# Interface.net
KiCad netlist of a schematic drawn in Altium Designer
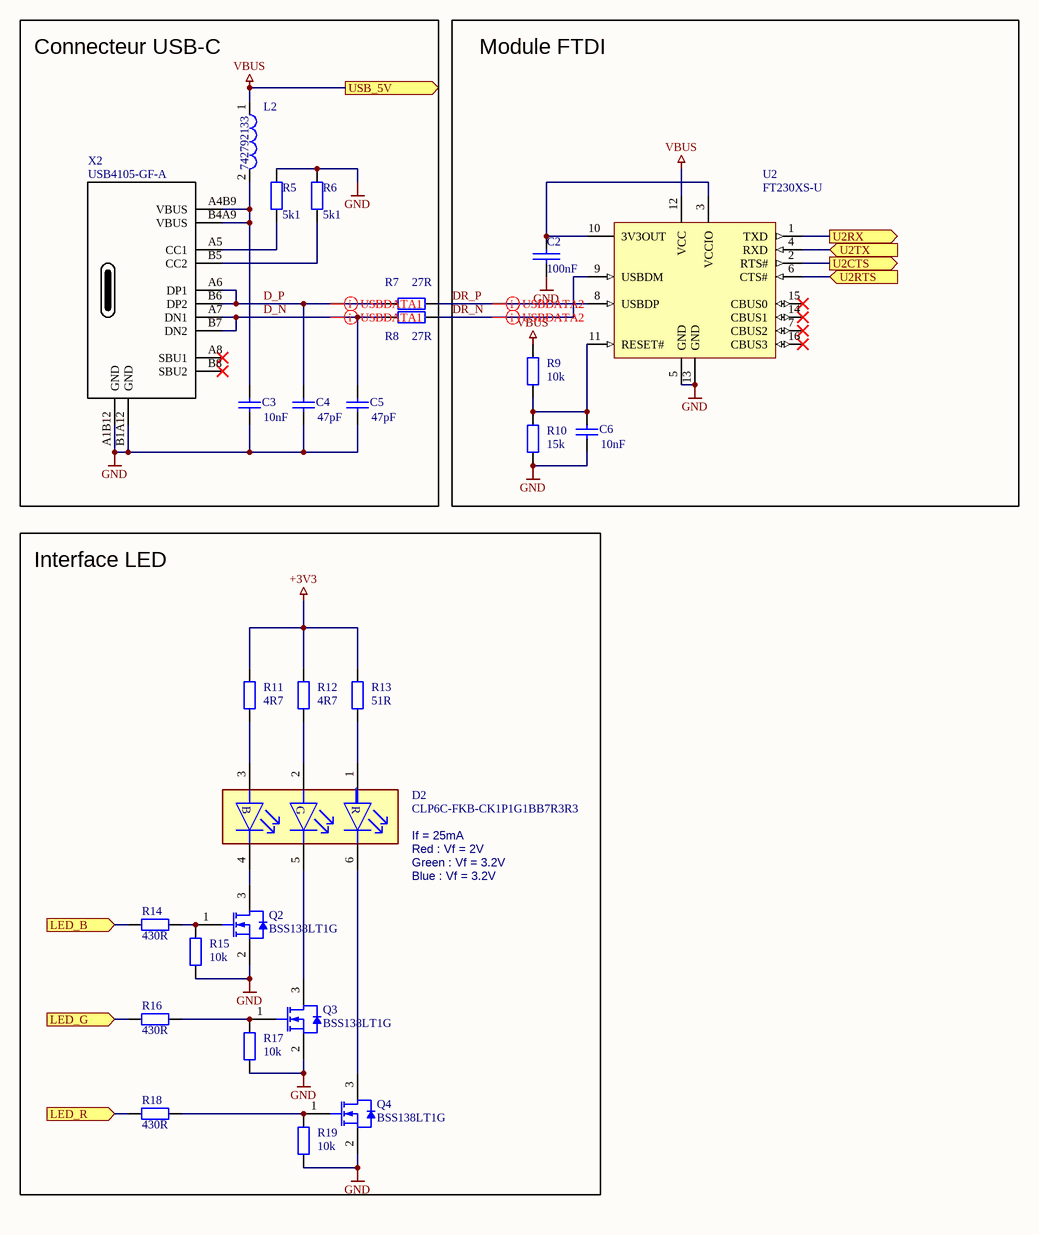
[diagram p0: Interface.SchDoc]

(export (version "E")
  (design (tool "Eeschema 10.0.6"))
  (components
    (comp (ref "C2") (value "100nF") (footprint "6-0805_L") (libsource (lib "*") (part "C")))
    (comp (ref "C3")
      (value "10nF")
      (footprint "6-0805_L")
      (description "Capacitor")
      (fields (field (name "PUBLISHER") "Altium Limited"))
      (libsource (lib "Miscellaneous Devices") (part "Cap"))
    )
    (comp (ref "C4")
      (value "47pF")
      (footprint "6-0805_L")
      (description "Capacitor")
      (fields (field (name "PUBLISHER") "Altium Limited"))
      (libsource (lib "Miscellaneous Devices") (part "Cap"))
    )
    (comp (ref "C5")
      (value "47pF")
      (footprint "6-0805_L")
      (description "Capacitor")
      (fields (field (name "PUBLISHER") "Altium Limited"))
      (libsource (lib "Miscellaneous Devices") (part "Cap"))
    )
    (comp (ref "C6")
      (value "10nF")
      (footprint "6-0805_L")
      (description "Capacitor")
      (fields (field (name "PUBLISHER") "Altium Limited"))
      (libsource (lib "Miscellaneous Devices") (part "Cap"))
    )
    (comp (ref "D2")
      (value "CLP6C-FKB-CK1P1G1BB7R3R3")
      (footprint "FP-CLP6C-FKB-CK1P1G1BB7R3-MFG")
      (description "LED RGB DIFFUSED 6PLCC SMD")
      (libsource (lib "Altium Content Vault") (part "c733277760584c2f8213bc00e84e6de"))
    )
    (comp (ref "L2")
      (value "742792133")
      (footprint "SMD-1206")
      (description "SMD EMI Suppression Ferrite Bead WE-CBF, Z = 600 Ohm")
      (libsource (lib "Altium Content Vault") (part "PAS-IND-INDUCTOR-2"))
    )
    (comp (ref "Q2")
      (value "BSS138LT1G")
      (footprint "ONSC-SOT-23-3-318-08_V")
      (description "Power MOSFET, 200 mA, 50 V, N-Channel, 3-Pin SOT-23, Pb-Free, Tape and Reel")
      (fields (field (name "MANUFACTURER") "On Semiconductor"))
      (libsource (lib "Altium Content Vault") (part "ONSC-NMOS-G1S2D3-3"))
    )
    (comp (ref "Q3")
      (value "BSS138LT1G")
      (footprint "ONSC-SOT-23-3-318-08_V")
      (description "Power MOSFET, 200 mA, 50 V, N-Channel, 3-Pin SOT-23, Pb-Free, Tape and Reel")
      (fields (field (name "MANUFACTURER") "On Semiconductor"))
      (libsource (lib "Altium Content Vault") (part "ONSC-NMOS-G1S2D3-3"))
    )
    (comp (ref "Q4")
      (value "BSS138LT1G")
      (footprint "ONSC-SOT-23-3-318-08_V")
      (description "Power MOSFET, 200 mA, 50 V, N-Channel, 3-Pin SOT-23, Pb-Free, Tape and Reel")
      (fields (field (name "MANUFACTURER") "On Semiconductor"))
      (libsource (lib "Altium Content Vault") (part "ONSC-NMOS-G1S2D3-3"))
    )
    (comp (ref "R5")
      (value "5k1")
      (footprint "6-0805_L")
      (description "Res 0805")
      (fields (field (name "PUBLISHER") "Altium Limited"))
      (libsource (lib "") (part "Res2_1"))
    )
    (comp (ref "R6")
      (value "5k1")
      (footprint "6-0805_L")
      (description "Res 0805")
      (fields (field (name "PUBLISHER") "Altium Limited"))
      (libsource (lib "") (part "Res2_1"))
    )
    (comp (ref "R7")
      (value "27R")
      (footprint "6-0805_L")
      (description "Res 0805")
      (fields (field (name "PUBLISHER") "Altium Limited"))
      (libsource (lib "") (part "Res2_2"))
    )
    (comp (ref "R8")
      (value "27R")
      (footprint "6-0805_L")
      (description "Res 0805")
      (fields (field (name "PUBLISHER") "Altium Limited"))
      (libsource (lib "") (part "Res2_2"))
    )
    (comp (ref "R9")
      (value "10k")
      (footprint "6-0805_L")
      (description "Res 0805")
      (fields (field (name "PUBLISHER") "Altium Limited"))
      (libsource (lib "") (part "Res2_1"))
    )
    (comp (ref "R10")
      (value "15k")
      (footprint "6-0805_L")
      (description "Res 0805")
      (fields (field (name "PUBLISHER") "Altium Limited"))
      (libsource (lib "") (part "Res2_1"))
    )
    (comp (ref "R11")
      (value "4R7")
      (footprint "6-0805_L")
      (description "Res 0805")
      (fields (field (name "PUBLISHER") "Altium Limited"))
      (libsource (lib "") (part "Res2_1"))
    )
    (comp (ref "R12")
      (value "4R7")
      (footprint "6-0805_L")
      (description "Res 0805")
      (fields (field (name "PUBLISHER") "Altium Limited"))
      (libsource (lib "") (part "Res2_1"))
    )
    (comp (ref "R13")
      (value "51R")
      (footprint "6-0805_L")
      (description "Res 0805")
      (fields (field (name "PUBLISHER") "Altium Limited"))
      (libsource (lib "") (part "Res2_1"))
    )
    (comp (ref "R14")
      (value "430R")
      (footprint "6-0805_L")
      (description "Res 0805")
      (fields (field (name "PUBLISHER") "Altium Limited"))
      (libsource (lib "Miscellaneous Devices") (part "Res2"))
    )
    (comp (ref "R15")
      (value "10k")
      (footprint "6-0805_L")
      (description "Res 0805")
      (fields (field (name "PUBLISHER") "Altium Limited"))
      (libsource (lib "") (part "Res2_1"))
    )
    (comp (ref "R16")
      (value "430R")
      (footprint "6-0805_L")
      (description "Res 0805")
      (fields (field (name "PUBLISHER") "Altium Limited"))
      (libsource (lib "Miscellaneous Devices") (part "Res2"))
    )
    (comp (ref "R17")
      (value "10k")
      (footprint "6-0805_L")
      (description "Res 0805")
      (fields (field (name "PUBLISHER") "Altium Limited"))
      (libsource (lib "") (part "Res2_1"))
    )
    (comp (ref "R18")
      (value "430R")
      (footprint "6-0805_L")
      (description "Res 0805")
      (fields (field (name "PUBLISHER") "Altium Limited"))
      (libsource (lib "Miscellaneous Devices") (part "Res2"))
    )
    (comp (ref "R19")
      (value "10k")
      (footprint "6-0805_L")
      (description "Res 0805")
      (fields (field (name "PUBLISHER") "Altium Limited"))
      (libsource (lib "") (part "Res2_1"))
    )
    (comp (ref "U2")
      (value "FT230XS-U")
      (footprint "SSOP-16_N")
      (fields (field (name "MANUFACTURER") "FTDI"))
      (libsource (lib "Altium Content Vault") (part "COM-USB-FT230XS-IL16"))
    )
    (comp (ref "X2")
      (value "USB4105-GF-A")
      (footprint "GCT_USB4105-GF-A")
      (description "USB4105-GF-A USB connector")
      (libsource (lib "2221-LIB") (part "USB-C Type 2.0"))
    )
  )
  (nets
    (net (code "1") (name "+3V3") (class "Default")
      (node (ref "R11") (pin "2") (pinfunction "2_2") (pintype "passive"))
      (node (ref "R12") (pin "2") (pinfunction "2_2") (pintype "passive"))
      (node (ref "R13") (pin "2") (pinfunction "2_2") (pintype "passive"))
    )
    (net (code "2") (name "/DR_N") (class "Default")
      (node (ref "R8") (pin "2") (pinfunction "2_2") (pintype "passive"))
      (node (ref "U2") (pin "9") (pinfunction "USBDM_9") (pintype "input"))
    )
    (net (code "3") (name "/DR_P") (class "Default")
      (node (ref "R7") (pin "2") (pinfunction "2_2") (pintype "passive"))
      (node (ref "U2") (pin "8") (pinfunction "USBDP_8") (pintype "input"))
    )
    (net (code "4") (name "/D_N") (class "Default")
      (node (ref "C5") (pin "2") (pinfunction "2_2") (pintype "passive"))
      (node (ref "R8") (pin "1") (pinfunction "1_1") (pintype "passive"))
      (node (ref "X2") (pin "A7") (pinfunction "DN1_A7") (pintype "passive"))
      (node (ref "X2") (pin "B7") (pinfunction "DN2_B7") (pintype "passive"))
    )
    (net (code "5") (name "/D_P") (class "Default")
      (node (ref "C4") (pin "2") (pinfunction "2_2") (pintype "passive"))
      (node (ref "R7") (pin "1") (pinfunction "1_1") (pintype "passive"))
      (node (ref "X2") (pin "A6") (pinfunction "DP1_A6") (pintype "passive"))
      (node (ref "X2") (pin "B6") (pinfunction "DP2_B6") (pintype "passive"))
    )
    (net (code "6") (name "/LED_B") (class "Default")
      (node (ref "R14") (pin "2") (pinfunction "2_2") (pintype "passive"))
    )
    (net (code "7") (name "/LED_G") (class "Default")
      (node (ref "R16") (pin "2") (pinfunction "2_2") (pintype "passive"))
    )
    (net (code "8") (name "/LED_R") (class "Default")
      (node (ref "R18") (pin "2") (pinfunction "2_2") (pintype "passive"))
    )
    (net (code "9") (name "/U2CTS") (class "Default")
      (node (ref "U2") (pin "2") (pinfunction "RTS#_2") (pintype "output"))
    )
    (net (code "10") (name "/U2RTS") (class "Default")
      (node (ref "U2") (pin "6") (pinfunction "CTS#_6") (pintype "input"))
    )
    (net (code "11") (name "/U2RX") (class "Default")
      (node (ref "U2") (pin "1") (pinfunction "TXD_1") (pintype "output"))
    )
    (net (code "12") (name "/U2TX") (class "Default")
      (node (ref "U2") (pin "4") (pinfunction "RXD_4") (pintype "input"))
    )
    (net (code "13") (name "GND") (class "Default")
      (node (ref "C2") (pin "2") (pinfunction "2_2") (pintype "passive"))
      (node (ref "C3") (pin "1") (pinfunction "1_1") (pintype "passive"))
      (node (ref "C4") (pin "1") (pinfunction "1_1") (pintype "passive"))
      (node (ref "C5") (pin "1") (pinfunction "1_1") (pintype "passive"))
      (node (ref "C6") (pin "1") (pinfunction "1_1") (pintype "passive"))
      (node (ref "Q2") (pin "2") (pinfunction "S_2") (pintype "passive"))
      (node (ref "Q3") (pin "2") (pinfunction "S_2") (pintype "passive"))
      (node (ref "Q4") (pin "2") (pinfunction "S_2") (pintype "passive"))
      (node (ref "R10") (pin "1") (pinfunction "1_1") (pintype "passive"))
      (node (ref "R15") (pin "1") (pinfunction "1_1") (pintype "passive"))
      (node (ref "R17") (pin "1") (pinfunction "1_1") (pintype "passive"))
      (node (ref "R19") (pin "1") (pinfunction "1_1") (pintype "passive"))
      (node (ref "R5") (pin "2") (pinfunction "2_2") (pintype "passive"))
      (node (ref "R6") (pin "2") (pinfunction "2_2") (pintype "passive"))
      (node (ref "U2") (pin "13") (pinfunction "GND_13") (pintype "power_in"))
      (node (ref "U2") (pin "5") (pinfunction "GND_5") (pintype "power_in"))
      (node (ref "X2") (pin "A1B12") (pinfunction "GND_A1B12") (pintype "passive"))
      (node (ref "X2") (pin "B1A12") (pinfunction "GND_B1A12") (pintype "passive"))
    )
    (net (code "14") (name "Net-(C3-Pad2)") (class "Default")
      (node (ref "C3") (pin "2") (pinfunction "2_2") (pintype "passive"))
      (node (ref "L2") (pin "2") (pinfunction "2_2") (pintype "passive"))
      (node (ref "X2") (pin "A4B9") (pinfunction "VBUS_A4B9") (pintype "passive"))
      (node (ref "X2") (pin "B4A9") (pinfunction "VBUS_B4A9") (pintype "passive"))
    )
    (net (code "15") (name "Net-(D2-BLUE_A)") (class "Default")
      (node (ref "D2") (pin "3") (pinfunction "BLUE_A_3") (pintype "passive"))
      (node (ref "R11") (pin "1") (pinfunction "1_1") (pintype "passive"))
    )
    (net (code "16") (name "Net-(D2-BLUE_C)") (class "Default")
      (node (ref "D2") (pin "4") (pinfunction "BLUE_C_4") (pintype "passive"))
      (node (ref "Q2") (pin "3") (pinfunction "D_3") (pintype "passive"))
    )
    (net (code "17") (name "Net-(D2-GREEN_A)") (class "Default")
      (node (ref "D2") (pin "2") (pinfunction "GREEN_A_2") (pintype "passive"))
      (node (ref "R12") (pin "1") (pinfunction "1_1") (pintype "passive"))
    )
    (net (code "18") (name "Net-(D2-GREEN_C)") (class "Default")
      (node (ref "D2") (pin "5") (pinfunction "GREEN_C_5") (pintype "passive"))
      (node (ref "Q3") (pin "3") (pinfunction "D_3") (pintype "passive"))
    )
    (net (code "19") (name "Net-(D2-RED_A)") (class "Default")
      (node (ref "D2") (pin "1") (pinfunction "RED_A_1") (pintype "passive"))
      (node (ref "R13") (pin "1") (pinfunction "1_1") (pintype "passive"))
    )
    (net (code "20") (name "Net-(D2-RED_C)") (class "Default")
      (node (ref "D2") (pin "6") (pinfunction "RED_C_6") (pintype "passive"))
      (node (ref "Q4") (pin "3") (pinfunction "D_3") (pintype "passive"))
    )
    (net (code "21") (name "Net-(Q2-G)") (class "Default")
      (node (ref "Q2") (pin "1") (pinfunction "G_1") (pintype "passive"))
      (node (ref "R14") (pin "1") (pinfunction "1_1") (pintype "passive"))
      (node (ref "R15") (pin "2") (pinfunction "2_2") (pintype "passive"))
    )
    (net (code "22") (name "Net-(Q3-G)") (class "Default")
      (node (ref "Q3") (pin "1") (pinfunction "G_1") (pintype "passive"))
      (node (ref "R16") (pin "1") (pinfunction "1_1") (pintype "passive"))
      (node (ref "R17") (pin "2") (pinfunction "2_2") (pintype "passive"))
    )
    (net (code "23") (name "Net-(Q4-G)") (class "Default")
      (node (ref "Q4") (pin "1") (pinfunction "G_1") (pintype "passive"))
      (node (ref "R18") (pin "1") (pinfunction "1_1") (pintype "passive"))
      (node (ref "R19") (pin "2") (pinfunction "2_2") (pintype "passive"))
    )
    (net (code "24") (name "Net-(U2-3V3OUT)") (class "Default")
      (node (ref "C2") (pin "1") (pinfunction "1_1") (pintype "passive"))
      (node (ref "U2") (pin "10") (pinfunction "3V3OUT_10") (pintype "power_in"))
      (node (ref "U2") (pin "3") (pinfunction "VCCIO_3") (pintype "power_in"))
    )
    (net (code "25") (name "Net-(U2-RESET#)") (class "Default")
      (node (ref "C6") (pin "2") (pinfunction "2_2") (pintype "passive"))
      (node (ref "R10") (pin "2") (pinfunction "2_2") (pintype "passive"))
      (node (ref "R9") (pin "1") (pinfunction "1_1") (pintype "passive"))
      (node (ref "U2") (pin "11") (pinfunction "RESET#_11") (pintype "input"))
    )
    (net (code "26") (name "Net-(X2-CC1)") (class "Default")
      (node (ref "R5") (pin "1") (pinfunction "1_1") (pintype "passive"))
      (node (ref "X2") (pin "A5") (pinfunction "CC1_A5") (pintype "passive"))
    )
    (net (code "27") (name "Net-(X2-CC2)") (class "Default")
      (node (ref "R6") (pin "1") (pinfunction "1_1") (pintype "passive"))
      (node (ref "X2") (pin "B5") (pinfunction "CC2_B5") (pintype "passive"))
    )
    (net (code "28") (name "VBUS") (class "Default")
      (node (ref "L2") (pin "1") (pinfunction "1_1") (pintype "passive"))
      (node (ref "R9") (pin "2") (pinfunction "2_2") (pintype "passive"))
      (node (ref "U2") (pin "12") (pinfunction "VCC_12") (pintype "power_in"))
    )
    (net (code "29") (name "unconnected-(U2-CBUS0-Pad15)") (class "Default")
      (node (ref "U2") (pin "15") (pinfunction "CBUS0_15") (pintype "bidirectional+no_connect"))
    )
    (net (code "30") (name "unconnected-(U2-CBUS1-Pad14)") (class "Default")
      (node (ref "U2") (pin "14") (pinfunction "CBUS1_14") (pintype "bidirectional+no_connect"))
    )
    (net (code "31") (name "unconnected-(U2-CBUS2-Pad7)") (class "Default")
      (node (ref "U2") (pin "7") (pinfunction "CBUS2_7") (pintype "bidirectional+no_connect"))
    )
    (net (code "32") (name "unconnected-(U2-CBUS3-Pad16)") (class "Default")
      (node (ref "U2") (pin "16") (pinfunction "CBUS3_16") (pintype "bidirectional+no_connect"))
    )
    (net (code "33") (name "unconnected-(X2-SBU1-PadA8)") (class "Default")
      (node (ref "X2") (pin "A8") (pinfunction "SBU1_A8") (pintype "passive+no_connect"))
    )
    (net (code "34") (name "unconnected-(X2-SBU2-PadB8)") (class "Default")
      (node (ref "X2") (pin "B8") (pinfunction "SBU2_B8") (pintype "passive+no_connect"))
    )
  )
)
